# honda_type1.net
KiCad netlist of a schematic drawn in EAGLE
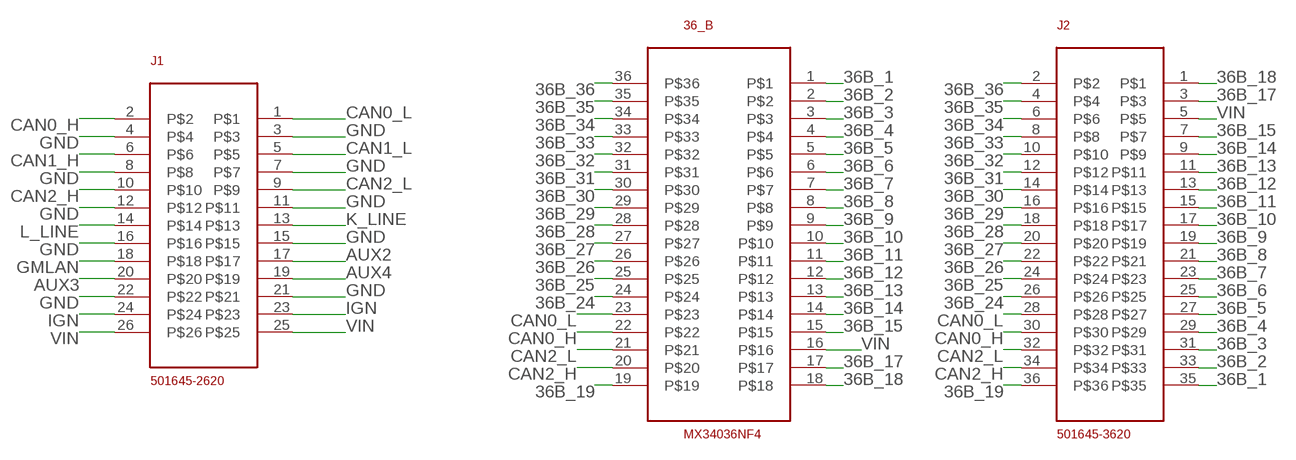
[diagram p0: schematic, sheet 1]

(export (version "E")
  (design (tool "Eeschema 10.0.6"))
  (components
    (comp (ref "36_B")
      (value "MX34036NF4")
      (footprint "eagle-import:MX34036NF2")
      (libsource (lib "eagle-import") (part "MX34036NF4"))
    )
    (comp (ref "J1")
      (value "501645-2620")
      (footprint "eagle-import:501645-2620")
      (libsource (lib "eagle-import") (part "501645-2620"))
    )
    (comp (ref "J2")
      (value "501645-3620")
      (footprint "eagle-import:501645-3620")
      (libsource (lib "eagle-import") (part "501645-3620"))
    )
  )
  (nets
    (net (code "1") (name "36B_1") (class "Default")
      (node (ref "36_B") (pin "1") (pinfunction "P$1_1") (pintype "bidirectional"))
      (node (ref "J2") (pin "35") (pinfunction "P$35_35") (pintype "bidirectional"))
    )
    (net (code "2") (name "36B_2") (class "Default")
      (node (ref "36_B") (pin "2") (pinfunction "P$2_2") (pintype "bidirectional"))
      (node (ref "J2") (pin "33") (pinfunction "P$33_33") (pintype "bidirectional"))
    )
    (net (code "3") (name "36B_3") (class "Default")
      (node (ref "36_B") (pin "3") (pinfunction "P$3_3") (pintype "bidirectional"))
      (node (ref "J2") (pin "31") (pinfunction "P$31_31") (pintype "bidirectional"))
    )
    (net (code "4") (name "36B_4") (class "Default")
      (node (ref "36_B") (pin "4") (pinfunction "P$4_4") (pintype "bidirectional"))
      (node (ref "J2") (pin "29") (pinfunction "P$29_29") (pintype "bidirectional"))
    )
    (net (code "5") (name "36B_5") (class "Default")
      (node (ref "36_B") (pin "5") (pinfunction "P$5_5") (pintype "bidirectional"))
      (node (ref "J2") (pin "27") (pinfunction "P$27_27") (pintype "bidirectional"))
    )
    (net (code "6") (name "36B_6") (class "Default")
      (node (ref "36_B") (pin "6") (pinfunction "P$6_6") (pintype "bidirectional"))
      (node (ref "J2") (pin "25") (pinfunction "P$25_25") (pintype "bidirectional"))
    )
    (net (code "7") (name "36B_7") (class "Default")
      (node (ref "36_B") (pin "7") (pinfunction "P$7_7") (pintype "bidirectional"))
      (node (ref "J2") (pin "23") (pinfunction "P$23_23") (pintype "bidirectional"))
    )
    (net (code "8") (name "36B_8") (class "Default")
      (node (ref "36_B") (pin "8") (pinfunction "P$8_8") (pintype "bidirectional"))
      (node (ref "J2") (pin "21") (pinfunction "P$21_21") (pintype "bidirectional"))
    )
    (net (code "9") (name "36B_9") (class "Default")
      (node (ref "36_B") (pin "9") (pinfunction "P$9_9") (pintype "bidirectional"))
      (node (ref "J2") (pin "19") (pinfunction "P$19_19") (pintype "bidirectional"))
    )
    (net (code "10") (name "36B_10") (class "Default")
      (node (ref "36_B") (pin "10") (pinfunction "P$10_10") (pintype "bidirectional"))
      (node (ref "J2") (pin "17") (pinfunction "P$17_17") (pintype "bidirectional"))
    )
    (net (code "11") (name "36B_11") (class "Default")
      (node (ref "36_B") (pin "11") (pinfunction "P$11_11") (pintype "bidirectional"))
      (node (ref "J2") (pin "15") (pinfunction "P$15_15") (pintype "bidirectional"))
    )
    (net (code "12") (name "36B_12") (class "Default")
      (node (ref "36_B") (pin "12") (pinfunction "P$12_12") (pintype "bidirectional"))
      (node (ref "J2") (pin "13") (pinfunction "P$13_13") (pintype "bidirectional"))
    )
    (net (code "13") (name "36B_13") (class "Default")
      (node (ref "36_B") (pin "13") (pinfunction "P$13_13") (pintype "bidirectional"))
      (node (ref "J2") (pin "11") (pinfunction "P$11_11") (pintype "bidirectional"))
    )
    (net (code "14") (name "36B_14") (class "Default")
      (node (ref "36_B") (pin "14") (pinfunction "P$14_14") (pintype "bidirectional"))
      (node (ref "J2") (pin "9") (pinfunction "P$9_9") (pintype "bidirectional"))
    )
    (net (code "15") (name "36B_15") (class "Default")
      (node (ref "36_B") (pin "15") (pinfunction "P$15_15") (pintype "bidirectional"))
      (node (ref "J2") (pin "7") (pinfunction "P$7_7") (pintype "bidirectional"))
    )
    (net (code "16") (name "36B_17") (class "Default")
      (node (ref "36_B") (pin "17") (pinfunction "P$17_17") (pintype "bidirectional"))
      (node (ref "J2") (pin "3") (pinfunction "P$3_3") (pintype "bidirectional"))
    )
    (net (code "17") (name "36B_18") (class "Default")
      (node (ref "36_B") (pin "18") (pinfunction "P$18_18") (pintype "bidirectional"))
      (node (ref "J2") (pin "1") (pinfunction "P$1_1") (pintype "bidirectional"))
    )
    (net (code "18") (name "36B_19") (class "Default")
      (node (ref "36_B") (pin "19") (pinfunction "P$19_19") (pintype "bidirectional"))
      (node (ref "J2") (pin "36") (pinfunction "P$36_36") (pintype "bidirectional"))
    )
    (net (code "19") (name "36B_24") (class "Default")
      (node (ref "36_B") (pin "24") (pinfunction "P$24_24") (pintype "bidirectional"))
      (node (ref "J2") (pin "26") (pinfunction "P$26_26") (pintype "bidirectional"))
    )
    (net (code "20") (name "36B_25") (class "Default")
      (node (ref "36_B") (pin "25") (pinfunction "P$25_25") (pintype "bidirectional"))
      (node (ref "J2") (pin "24") (pinfunction "P$24_24") (pintype "bidirectional"))
    )
    (net (code "21") (name "36B_26") (class "Default")
      (node (ref "36_B") (pin "26") (pinfunction "P$26_26") (pintype "bidirectional"))
      (node (ref "J2") (pin "22") (pinfunction "P$22_22") (pintype "bidirectional"))
    )
    (net (code "22") (name "36B_27") (class "Default")
      (node (ref "36_B") (pin "27") (pinfunction "P$27_27") (pintype "bidirectional"))
      (node (ref "J2") (pin "20") (pinfunction "P$20_20") (pintype "bidirectional"))
    )
    (net (code "23") (name "36B_28") (class "Default")
      (node (ref "36_B") (pin "28") (pinfunction "P$28_28") (pintype "bidirectional"))
      (node (ref "J2") (pin "18") (pinfunction "P$18_18") (pintype "bidirectional"))
    )
    (net (code "24") (name "36B_29") (class "Default")
      (node (ref "36_B") (pin "29") (pinfunction "P$29_29") (pintype "bidirectional"))
      (node (ref "J2") (pin "16") (pinfunction "P$16_16") (pintype "bidirectional"))
    )
    (net (code "25") (name "36B_30") (class "Default")
      (node (ref "36_B") (pin "30") (pinfunction "P$30_30") (pintype "bidirectional"))
      (node (ref "J2") (pin "14") (pinfunction "P$14_14") (pintype "bidirectional"))
    )
    (net (code "26") (name "36B_31") (class "Default")
      (node (ref "36_B") (pin "31") (pinfunction "P$31_31") (pintype "bidirectional"))
      (node (ref "J2") (pin "12") (pinfunction "P$12_12") (pintype "bidirectional"))
    )
    (net (code "27") (name "36B_32") (class "Default")
      (node (ref "36_B") (pin "32") (pinfunction "P$32_32") (pintype "bidirectional"))
      (node (ref "J2") (pin "10") (pinfunction "P$10_10") (pintype "bidirectional"))
    )
    (net (code "28") (name "36B_33") (class "Default")
      (node (ref "36_B") (pin "33") (pinfunction "P$33_33") (pintype "bidirectional"))
      (node (ref "J2") (pin "8") (pinfunction "P$8_8") (pintype "bidirectional"))
    )
    (net (code "29") (name "36B_34") (class "Default")
      (node (ref "36_B") (pin "34") (pinfunction "P$34_34") (pintype "bidirectional"))
      (node (ref "J2") (pin "6") (pinfunction "P$6_6") (pintype "bidirectional"))
    )
    (net (code "30") (name "36B_35") (class "Default")
      (node (ref "36_B") (pin "35") (pinfunction "P$35_35") (pintype "bidirectional"))
      (node (ref "J2") (pin "4") (pinfunction "P$4_4") (pintype "bidirectional"))
    )
    (net (code "31") (name "36B_36") (class "Default")
      (node (ref "36_B") (pin "36") (pinfunction "P$36_36") (pintype "bidirectional"))
      (node (ref "J2") (pin "2") (pinfunction "P$2_2") (pintype "bidirectional"))
    )
    (net (code "32") (name "AUX2") (class "Default")
      (node (ref "J1") (pin "17") (pinfunction "P$17_17") (pintype "bidirectional"))
    )
    (net (code "33") (name "AUX3") (class "Default")
      (node (ref "J1") (pin "20") (pinfunction "P$20_20") (pintype "bidirectional"))
    )
    (net (code "34") (name "AUX4") (class "Default")
      (node (ref "J1") (pin "19") (pinfunction "P$19_19") (pintype "bidirectional"))
    )
    (net (code "35") (name "CAN0_H") (class "Default")
      (node (ref "36_B") (pin "22") (pinfunction "P$22_22") (pintype "bidirectional"))
      (node (ref "J1") (pin "2") (pinfunction "P$2_2") (pintype "bidirectional"))
      (node (ref "J2") (pin "30") (pinfunction "P$30_30") (pintype "bidirectional"))
    )
    (net (code "36") (name "CAN0_L") (class "Default")
      (node (ref "36_B") (pin "23") (pinfunction "P$23_23") (pintype "bidirectional"))
      (node (ref "J1") (pin "1") (pinfunction "P$1_1") (pintype "bidirectional"))
      (node (ref "J2") (pin "28") (pinfunction "P$28_28") (pintype "bidirectional"))
    )
    (net (code "37") (name "CAN1_H") (class "Default")
      (node (ref "J1") (pin "6") (pinfunction "P$6_6") (pintype "bidirectional"))
    )
    (net (code "38") (name "CAN1_L") (class "Default")
      (node (ref "J1") (pin "5") (pinfunction "P$5_5") (pintype "bidirectional"))
    )
    (net (code "39") (name "CAN2_H") (class "Default")
      (node (ref "36_B") (pin "20") (pinfunction "P$20_20") (pintype "bidirectional"))
      (node (ref "J1") (pin "10") (pinfunction "P$10_10") (pintype "bidirectional"))
      (node (ref "J2") (pin "34") (pinfunction "P$34_34") (pintype "bidirectional"))
    )
    (net (code "40") (name "CAN2_L") (class "Default")
      (node (ref "36_B") (pin "21") (pinfunction "P$21_21") (pintype "bidirectional"))
      (node (ref "J1") (pin "9") (pinfunction "P$9_9") (pintype "bidirectional"))
      (node (ref "J2") (pin "32") (pinfunction "P$32_32") (pintype "bidirectional"))
    )
    (net (code "41") (name "GMLAN") (class "Default")
      (node (ref "J1") (pin "18") (pinfunction "P$18_18") (pintype "bidirectional"))
    )
    (net (code "42") (name "GND") (class "Default")
      (node (ref "J1") (pin "11") (pinfunction "P$11_11") (pintype "bidirectional"))
      (node (ref "J1") (pin "12") (pinfunction "P$12_12") (pintype "bidirectional"))
      (node (ref "J1") (pin "15") (pinfunction "P$15_15") (pintype "bidirectional"))
      (node (ref "J1") (pin "16") (pinfunction "P$16_16") (pintype "bidirectional"))
      (node (ref "J1") (pin "21") (pinfunction "P$21_21") (pintype "bidirectional"))
      (node (ref "J1") (pin "22") (pinfunction "P$22_22") (pintype "bidirectional"))
      (node (ref "J1") (pin "3") (pinfunction "P$3_3") (pintype "bidirectional"))
      (node (ref "J1") (pin "4") (pinfunction "P$4_4") (pintype "bidirectional"))
      (node (ref "J1") (pin "7") (pinfunction "P$7_7") (pintype "bidirectional"))
      (node (ref "J1") (pin "8") (pinfunction "P$8_8") (pintype "bidirectional"))
    )
    (net (code "43") (name "IGN") (class "Default")
      (node (ref "J1") (pin "23") (pinfunction "P$23_23") (pintype "bidirectional"))
      (node (ref "J1") (pin "24") (pinfunction "P$24_24") (pintype "bidirectional"))
    )
    (net (code "44") (name "K_LINE") (class "Default")
      (node (ref "J1") (pin "13") (pinfunction "P$13_13") (pintype "bidirectional"))
    )
    (net (code "45") (name "L_LINE") (class "Default")
      (node (ref "J1") (pin "14") (pinfunction "P$14_14") (pintype "bidirectional"))
    )
    (net (code "46") (name "VIN") (class "Default")
      (node (ref "36_B") (pin "16") (pinfunction "P$16_16") (pintype "bidirectional"))
      (node (ref "J1") (pin "25") (pinfunction "P$25_25") (pintype "bidirectional"))
      (node (ref "J1") (pin "26") (pinfunction "P$26_26") (pintype "bidirectional"))
      (node (ref "J2") (pin "5") (pinfunction "P$5_5") (pintype "bidirectional"))
    )
  )
)
